# Logger_L072CB_LiPo_Flash_EEprom.net
KiCad netlist of a schematic drawn in Altium Designer
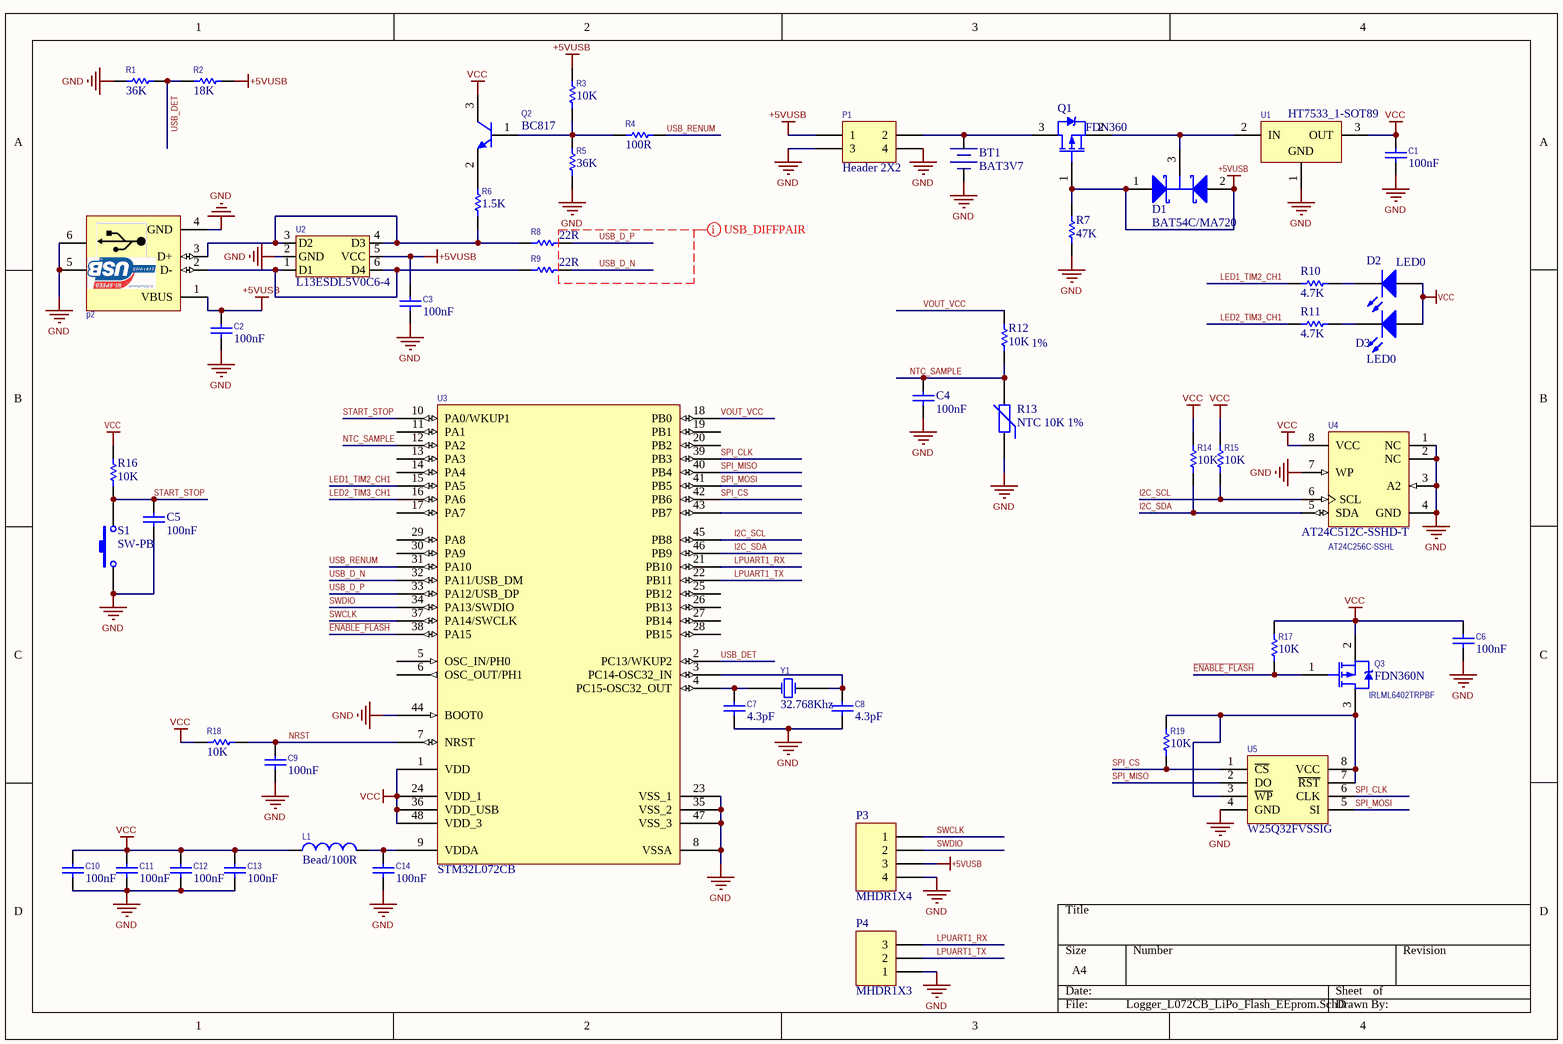
[diagram p0: Logger_L072CB_LiPo_Flash_EEprom.SchDoc]

(export (version "E")
  (design (tool "Eeschema 10.0.6"))
  (components
    (comp (ref "BT1")
      (value "BAT3V7")
      (footprint "BTH2032-smd")
      (description "Battry Backup")
      (fields (field (name "DESIGNER") "Abbas Basereh"))
      (libsource (lib "Mofidi3D") (part "Battry Backup"))
    )
    (comp (ref "C1")
      (value "100nF")
      (footprint "CAP0603")
      (description "Capacitor")
      (fields (field (name "PUBLISHER") "Altium Limited"))
      (libsource (lib "Miscellaneous Devices") (part "Cap"))
    )
    (comp (ref "C2")
      (value "100nF")
      (footprint "CAP0603")
      (description "Capacitor")
      (fields (field (name "PUBLISHER") "Altium Limited"))
      (libsource (lib "Miscellaneous Devices") (part "Cap"))
    )
    (comp (ref "C3")
      (value "100nF")
      (footprint "CAP0603")
      (description "Capacitor")
      (fields (field (name "PUBLISHER") "Altium Limited"))
      (libsource (lib "Miscellaneous Devices") (part "Cap"))
    )
    (comp (ref "C4")
      (value "100nF")
      (footprint "CAP0603")
      (description "Capacitor")
      (fields (field (name "PUBLISHER") "Altium Limited"))
      (libsource (lib "Miscellaneous Devices") (part "Cap"))
    )
    (comp (ref "C5")
      (value "100nF")
      (footprint "CAP0603")
      (description "Capacitor")
      (fields (field (name "PUBLISHER") "Altium Limited"))
      (libsource (lib "Miscellaneous Devices") (part "Cap"))
    )
    (comp (ref "C6")
      (value "100nF")
      (footprint "CAP0603")
      (description "Capacitor")
      (fields (field (name "PUBLISHER") "Altium Limited"))
      (libsource (lib "Miscellaneous Devices") (part "Cap"))
    )
    (comp (ref "C7")
      (value "4.3pF")
      (footprint "CAP0603")
      (description "Capacitor")
      (fields (field (name "PUBLISHER") "Altium Limited"))
      (libsource (lib "Miscellaneous Devices") (part "Cap"))
    )
    (comp (ref "C8")
      (value "4.3pF")
      (footprint "CAP0603")
      (description "Capacitor")
      (fields (field (name "PUBLISHER") "Altium Limited"))
      (libsource (lib "Miscellaneous Devices") (part "Cap"))
    )
    (comp (ref "C9")
      (value "100nF")
      (footprint "CAP0603")
      (description "Capacitor")
      (fields (field (name "PUBLISHER") "Altium Limited"))
      (libsource (lib "Miscellaneous Devices") (part "Cap"))
    )
    (comp (ref "C10")
      (value "100nF")
      (footprint "CAP0603")
      (description "Capacitor")
      (fields (field (name "PUBLISHER") "Altium Limited"))
      (libsource (lib "Miscellaneous Devices") (part "Cap"))
    )
    (comp (ref "C11")
      (value "100nF")
      (footprint "CAP0603")
      (description "Capacitor")
      (fields (field (name "PUBLISHER") "Altium Limited"))
      (libsource (lib "Miscellaneous Devices") (part "Cap"))
    )
    (comp (ref "C12")
      (value "100nF")
      (footprint "CAP0603")
      (description "Capacitor")
      (fields (field (name "PUBLISHER") "Altium Limited"))
      (libsource (lib "Miscellaneous Devices") (part "Cap"))
    )
    (comp (ref "C13")
      (value "100nF")
      (footprint "CAP0603")
      (description "Capacitor")
      (fields (field (name "PUBLISHER") "Altium Limited"))
      (libsource (lib "Miscellaneous Devices") (part "Cap"))
    )
    (comp (ref "C14")
      (value "100nF")
      (footprint "CAP0603")
      (description "Capacitor")
      (fields (field (name "PUBLISHER") "Altium Limited"))
      (libsource (lib "Miscellaneous Devices") (part "Cap"))
    )
    (comp (ref "D1")
      (value "BAT54C/MA720")
      (footprint "SOT23_N")
      (description "Schottky Barrier Double Diode")
      (fields (field (name "PUBLISHER") "Altium Limited"))
      (libsource (lib "Philips Discrete Diode - Schottky") (part "BAT54C"))
    )
    (comp (ref "D2")
      (value "LED0")
      (footprint "LED_0805")
      (description "Typical INFRARED GaAs LED")
      (fields (field (name "PUBLISHER") "Altium Limited"))
      (libsource (lib "Miscellaneous Devices") (part "LED0"))
    )
    (comp (ref "D3")
      (value "LED0")
      (footprint "LED_0805")
      (description "Typical INFRARED GaAs LED")
      (fields (field (name "PUBLISHER") "Altium Limited"))
      (libsource (lib "Miscellaneous Devices") (part "LED0"))
    )
    (comp (ref "L1")
      (value "Bead/100R")
      (footprint "IND0805")
      (description "Inductor")
      (fields (field (name "PUBLISHER") "Altium Limited"))
      (libsource (lib "Miscellaneous Devices") (part "Inductor"))
    )
    (comp (ref "P1")
      (value "Header 2X2")
      (footprint "HDR2X2")
      (description "Header, 2-Pin, Dual row")
      (fields (field (name "PUBLISHER") "Altium Limited"))
      (libsource (lib "Miscellaneous Connectors") (part "Header 2X2"))
    )
    (comp (ref "p2")
      (value "USB Connector")
      (footprint "USB A TYPE Right Angle")
      (description "USB Connector-A Type")
      (fields (field (name "DESIGNER") "ABBAS BASEREH") (field (name "PUBLISHER") "ABBAS BASEREH"))
      (libsource (lib "Mofidi3D") (part "USB A CONNECTOR"))
    )
    (comp (ref "P3")
      (value "MHDR1X4")
      (footprint "HDR1X4")
      (description "Header, 4-Pin")
      (fields (field (name "PUBLISHER") "Altium Limited"))
      (libsource (lib "Miscellaneous Connectors") (part "MHDR1X4"))
    )
    (comp (ref "P4")
      (value "MHDR1X3")
      (footprint "HDR1X3")
      (description "Header, 3-Pin")
      (fields (field (name "PUBLISHER") "Altium Limited"))
      (libsource (lib "Miscellaneous Connectors") (part "MHDR1X3"))
    )
    (comp (ref "Q1")
      (value "FDN360")
      (footprint "SOT-23_N")
      (description "HEXFET Power MOSFET")
      (fields (field (name "PUBLISHER") "Altium Limited"))
      (libsource (lib "IR Discrete MOSFET - Power") (part "IRLML5103"))
    )
    (comp (ref "Q2")
      (value "BC817")
      (footprint "SOT23_N")
      (description "45 V, 500 mA NPN general-purpose transistors")
      (fields (field (name "PUBLISHER") "Abbas Basereh"))
      (libsource (lib "Mofidi3D") (part "BC817"))
    )
    (comp (ref "Q3")
      (value "FDN360N")
      (footprint "Micro3_N")
      (description "HEXFET Power MOSFET")
      (fields (field (name "PUBLISHER") "Altium Limited"))
      (libsource (lib "IR Discrete MOSFET - Power") (part "IRLML6401"))
    )
    (comp (ref "R1")
      (value "36K")
      (footprint "RES0603")
      (description "Resistor")
      (fields (field (name "PUBLISHER") "Altium Limited"))
      (libsource (lib "Miscellaneous Devices") (part "Res1"))
    )
    (comp (ref "R2")
      (value "18K")
      (footprint "RES0603")
      (description "Resistor")
      (fields (field (name "PUBLISHER") "Altium Limited"))
      (libsource (lib "Miscellaneous Devices") (part "Res1"))
    )
    (comp (ref "R3")
      (value "10K")
      (footprint "RES0603")
      (description "Resistor")
      (fields (field (name "PUBLISHER") "Altium Limited"))
      (libsource (lib "Miscellaneous Devices") (part "Res1"))
    )
    (comp (ref "R4")
      (value "100R")
      (footprint "RES0603")
      (description "Resistor")
      (fields (field (name "PUBLISHER") "Altium Limited"))
      (libsource (lib "Miscellaneous Devices") (part "Res1"))
    )
    (comp (ref "R5")
      (value "36K")
      (footprint "RES0603")
      (description "Resistor")
      (fields (field (name "PUBLISHER") "Altium Limited"))
      (libsource (lib "Miscellaneous Devices") (part "Res1"))
    )
    (comp (ref "R6")
      (value "1.5K")
      (footprint "RES0603")
      (description "Resistor")
      (fields (field (name "PUBLISHER") "Altium Limited"))
      (libsource (lib "Miscellaneous Devices") (part "Res1"))
    )
    (comp (ref "R7")
      (value "47K")
      (footprint "RES0603")
      (description "Resistor")
      (fields (field (name "Comment") "Res1") (field (name "PUBLISHER") "Altium Limited"))
      (libsource (lib "Miscellaneous Devices") (part "Res1"))
    )
    (comp (ref "R8")
      (value "22R")
      (footprint "RES0603")
      (description "Resistor")
      (fields (field (name "PUBLISHER") "Altium Limited"))
      (libsource (lib "Miscellaneous Devices") (part "Res1"))
    )
    (comp (ref "R9")
      (value "22R")
      (footprint "RES0603")
      (description "Resistor")
      (fields (field (name "PUBLISHER") "Altium Limited"))
      (libsource (lib "Miscellaneous Devices") (part "Res1"))
    )
    (comp (ref "R10")
      (value "4.7K")
      (footprint "RES0603")
      (description "Resistor")
      (fields (field (name "Comment") "Res1") (field (name "PUBLISHER") "Altium Limited"))
      (libsource (lib "Miscellaneous Devices") (part "Res1"))
    )
    (comp (ref "R11")
      (value "4.7K")
      (footprint "RES0603")
      (description "Resistor")
      (fields (field (name "Comment") "Res1") (field (name "PUBLISHER") "Altium Limited"))
      (libsource (lib "Miscellaneous Devices") (part "Res1"))
    )
    (comp (ref "R12")
      (value "1%")
      (footprint "RES0603")
      (description "Resistor")
      (fields (field (name "ALTIUM_VALUE") "10K") (field (name "PUBLISHER") "Altium Limited"))
      (libsource (lib "Miscellaneous Devices") (part "Res1"))
    )
    (comp (ref "R13")
      (value "NTC 10K 1%")
      (footprint "CAP_MLCC_RAD_0.1")
      (description "Varistor (Voltage-Sensitive Resistor)")
      (fields (field (name "PUBLISHER") "Altium Limited"))
      (libsource (lib "Miscellaneous Devices") (part "Res Varistor"))
    )
    (comp (ref "R14")
      (value "10K")
      (footprint "RES0603")
      (description "Resistor")
      (fields (field (name "PUBLISHER") "Altium Limited"))
      (libsource (lib "Miscellaneous Devices") (part "Res1"))
    )
    (comp (ref "R15")
      (value "10K")
      (footprint "RES0603")
      (description "Resistor")
      (fields (field (name "PUBLISHER") "Altium Limited"))
      (libsource (lib "Miscellaneous Devices") (part "Res1"))
    )
    (comp (ref "R16")
      (value "10K")
      (footprint "RES0603")
      (description "Resistor")
      (fields (field (name "PUBLISHER") "Altium Limited"))
      (libsource (lib "Miscellaneous Devices") (part "Res1"))
    )
    (comp (ref "R17")
      (value "10K")
      (footprint "RES0603")
      (description "Resistor")
      (fields (field (name "PUBLISHER") "Altium Limited"))
      (libsource (lib "Miscellaneous Devices") (part "Res1"))
    )
    (comp (ref "R18")
      (value "10K")
      (footprint "RES0603")
      (description "Resistor")
      (fields (field (name "PUBLISHER") "Altium Limited"))
      (libsource (lib "Miscellaneous Devices") (part "Res1"))
    )
    (comp (ref "R19")
      (value "10K")
      (footprint "RES0603")
      (description "Resistor")
      (fields (field (name "PUBLISHER") "Altium Limited"))
      (libsource (lib "Miscellaneous Devices") (part "Res1"))
    )
    (comp (ref "S1")
      (value "SW-PB")
      (footprint "SW-4PIN-SMD")
      (description "Switch")
      (fields (field (name "PUBLISHER") "Altium Limited"))
      (libsource (lib "Miscellaneous Devices") (part "SW-PB"))
    )
    (comp (ref "U1")
      (value "HT7533_1-SOT89")
      (footprint "SOT89N")
      (description "100mA Low Power LDO, Output Voltage 3.3V, SOT89 Pkg")
      (libsource (lib "Holtek Semiconductor Power Management") (part "HT7533_1-SOT89"))
    )
    (comp (ref "U2")
      (value "L13ESDL5V0C6-4")
      (footprint "Holtek Semiconductor Power Management:SOT23-6_M")
      (description "ESD PROTECTION DEVICE")
      (libsource (lib "Mofidi3D") (part "USBUFxxW6"))
    )
    (comp (ref "U3")
      (value "STM32L072CB")
      (footprint "LQFP48_N")
      (description "STM32 ARM-based 32-bit MCU with 64 Kbytes Flash, 48-pin LQFP, Industrial Temperature")
      (fields (field (name "PUBLISHER") "Altium Limited"))
      (libsource (lib "ST Microcontroller 32-Bit STM32") (part "STM32F103C8T6"))
    )
    (comp (ref "U4")
      (value "AT24C512C-SSHD-T")
      (footprint "SO-8N")
      (description "I2C-Compatible (2-wire) Serial EEPROM\r\n512-Kbit (65,536 x 8)")
      (fields (field (name "PUBLISHER") "Altium Limited"))
      (libsource (lib "Atmel Memory Serial EEPROM") (part "AT24C08BN-SP25-B"))
    )
    (comp (ref "U5")
      (value "W25Q32FVSSIG")
      (footprint "8S2_M")
      (description "SERIAL FLASH MEMORY WITH DUAL, QUAD SPI")
      (libsource (lib "Mofidi3D") (part "W25Q"))
    )
    (comp (ref "Y1")
      (value "32.768Khz")
      (footprint "CM415")
      (description "XTAL Crystal")
      (fields (field (name "DESIGNER") "ABBAS BASEREH"))
      (libsource (lib "Mofidi3D") (part "XTAL_Crystal"))
    )
  )
  (nets
    (net (code "1") (name "+5VUSB") (class "Default")
      (node (ref "C2") (pin "1") (pinfunction "1_1") (pintype "passive"))
      (node (ref "C3") (pin "2") (pinfunction "2_2") (pintype "passive"))
      (node (ref "D1") (pin "1") (pinfunction "A1_1") (pintype "passive"))
      (node (ref "D1") (pin "2") (pinfunction "A2_2") (pintype "passive"))
      (node (ref "P1") (pin "1") (pinfunction "1_1") (pintype "passive"))
      (node (ref "P3") (pin "3") (pinfunction "3_3") (pintype "passive"))
      (node (ref "Q1") (pin "1") (pinfunction "G_1") (pintype "passive"))
      (node (ref "R2") (pin "1") (pinfunction "1_1") (pintype "passive"))
      (node (ref "R3") (pin "1") (pinfunction "1_1") (pintype "passive"))
      (node (ref "R7") (pin "1") (pinfunction "1_1") (pintype "passive"))
      (node (ref "U2") (pin "5") (pinfunction "VCC_5") (pintype "passive"))
      (node (ref "p2") (pin "1") (pinfunction "VBUS_1") (pintype "power_in"))
    )
    (net (code "2") (name "/I2C_SCL") (class "Default")
      (node (ref "R15") (pin "2") (pinfunction "2_2") (pintype "passive"))
      (node (ref "U3") (pin "45") (pinfunction "PB8_45") (pintype "bidirectional"))
      (node (ref "U4") (pin "6") (pinfunction "SCL_6") (pintype "input"))
    )
    (net (code "3") (name "/I2C_SDA") (class "Default")
      (node (ref "R14") (pin "2") (pinfunction "2_2") (pintype "passive"))
      (node (ref "U3") (pin "46") (pinfunction "PB9_46") (pintype "bidirectional"))
      (node (ref "U4") (pin "5") (pinfunction "SDA_5") (pintype "bidirectional"))
    )
    (net (code "4") (name "/LED1_TIM2_CH1") (class "Default")
      (node (ref "R10") (pin "2") (pinfunction "2_2") (pintype "passive"))
      (node (ref "U3") (pin "15") (pinfunction "PA5_15") (pintype "bidirectional"))
    )
    (net (code "5") (name "/LED2_TIM3_CH1") (class "Default")
      (node (ref "R11") (pin "2") (pinfunction "2_2") (pintype "passive"))
      (node (ref "U3") (pin "16") (pinfunction "PA6_16") (pintype "bidirectional"))
    )
    (net (code "6") (name "/LPUART1_RX") (class "Default")
      (node (ref "P4") (pin "3") (pinfunction "3_3") (pintype "passive"))
      (node (ref "U3") (pin "21") (pinfunction "PB10_21") (pintype "bidirectional"))
    )
    (net (code "7") (name "/LPUART1_TX") (class "Default")
      (node (ref "P4") (pin "2") (pinfunction "2_2") (pintype "passive"))
      (node (ref "U3") (pin "22") (pinfunction "PB11_22") (pintype "bidirectional"))
    )
    (net (code "8") (name "/NRST") (class "Default")
      (node (ref "C9") (pin "1") (pinfunction "1_1") (pintype "passive"))
      (node (ref "R18") (pin "1") (pinfunction "1_1") (pintype "passive"))
      (node (ref "U3") (pin "7") (pinfunction "NRST_7") (pintype "bidirectional"))
    )
    (net (code "9") (name "/NTC_SAMPLE") (class "Default")
      (node (ref "C4") (pin "1") (pinfunction "1_1") (pintype "passive"))
      (node (ref "R12") (pin "2") (pinfunction "2_2") (pintype "passive"))
      (node (ref "R13") (pin "2") (pinfunction "2_2") (pintype "passive"))
      (node (ref "U3") (pin "12") (pinfunction "PA2_12") (pintype "bidirectional"))
    )
    (net (code "10") (name "/SPI_CLK") (class "Default")
      (node (ref "U3") (pin "39") (pinfunction "PB3_39") (pintype "bidirectional"))
      (node (ref "U5") (pin "6") (pinfunction "CLK_6") (pintype "passive"))
    )
    (net (code "11") (name "/SPI_CS") (class "Default")
      (node (ref "R19") (pin "2") (pinfunction "2_2") (pintype "passive"))
      (node (ref "U3") (pin "42") (pinfunction "PB6_42") (pintype "bidirectional"))
      (node (ref "U5") (pin "1") (pinfunction "~{CS}_1") (pintype "passive"))
    )
    (net (code "12") (name "/SPI_MISO") (class "Default")
      (node (ref "U3") (pin "40") (pinfunction "PB4_40") (pintype "bidirectional"))
      (node (ref "U5") (pin "2") (pinfunction "DO_2") (pintype "passive"))
    )
    (net (code "13") (name "/SPI_MOSI") (class "Default")
      (node (ref "U3") (pin "41") (pinfunction "PB5_41") (pintype "bidirectional"))
      (node (ref "U5") (pin "5") (pinfunction "SI_5") (pintype "passive"))
    )
    (net (code "14") (name "/START_STOP") (class "Default")
      (node (ref "C5") (pin "2") (pinfunction "2_2") (pintype "passive"))
      (node (ref "R16") (pin "1") (pinfunction "1_1") (pintype "passive"))
      (node (ref "S1") (pin "2") (pinfunction "2_2") (pintype "passive"))
      (node (ref "U3") (pin "10") (pinfunction "PA0/WKUP1_10") (pintype "bidirectional"))
    )
    (net (code "15") (name "/SWCLK") (class "Default")
      (node (ref "P3") (pin "1") (pinfunction "1_1") (pintype "passive"))
      (node (ref "U3") (pin "37") (pinfunction "PA14/SWCLK_37") (pintype "bidirectional"))
    )
    (net (code "16") (name "/SWDIO") (class "Default")
      (node (ref "P3") (pin "2") (pinfunction "2_2") (pintype "passive"))
      (node (ref "U3") (pin "34") (pinfunction "PA13/SWDIO_34") (pintype "bidirectional"))
    )
    (net (code "17") (name "/USB_DET") (class "Default")
      (node (ref "R1") (pin "2") (pinfunction "2_2") (pintype "passive"))
      (node (ref "R2") (pin "2") (pinfunction "2_2") (pintype "passive"))
      (node (ref "U3") (pin "2") (pinfunction "PC13/WKUP2_2") (pintype "bidirectional"))
    )
    (net (code "18") (name "/USB_D_N") (class "Default")
      (node (ref "R9") (pin "1") (pinfunction "1_1") (pintype "passive"))
      (node (ref "U3") (pin "32") (pinfunction "PA11/USB_DM_32") (pintype "bidirectional"))
    )
    (net (code "19") (name "/USB_D_P") (class "Default")
      (node (ref "R8") (pin "1") (pinfunction "1_1") (pintype "passive"))
      (node (ref "U3") (pin "33") (pinfunction "PA12/USB_DP_33") (pintype "bidirectional"))
    )
    (net (code "20") (name "/USB_RENUM") (class "Default")
      (node (ref "R4") (pin "1") (pinfunction "1_1") (pintype "passive"))
      (node (ref "U3") (pin "31") (pinfunction "PA10_31") (pintype "bidirectional"))
    )
    (net (code "21") (name "/VOUT_VCC") (class "Default")
      (node (ref "R12") (pin "1") (pinfunction "1_1") (pintype "passive"))
      (node (ref "U3") (pin "18") (pinfunction "PB0_18") (pintype "bidirectional"))
    )
    (net (code "22") (name "/~{ENABLE_FLASH}") (class "Default")
      (node (ref "Q3") (pin "1") (pinfunction "G_1") (pintype "passive"))
      (node (ref "R17") (pin "2") (pinfunction "2_2") (pintype "passive"))
      (node (ref "U3") (pin "38") (pinfunction "PA15_38") (pintype "bidirectional"))
    )
    (net (code "23") (name "GND") (class "Default")
      (node (ref "BT1") (pin "2") (pinfunction "-_2") (pintype "passive"))
      (node (ref "C1") (pin "2") (pinfunction "2_2") (pintype "passive"))
      (node (ref "C10") (pin "2") (pinfunction "2_2") (pintype "passive"))
      (node (ref "C11") (pin "2") (pinfunction "2_2") (pintype "passive"))
      (node (ref "C12") (pin "2") (pinfunction "2_2") (pintype "passive"))
      (node (ref "C13") (pin "2") (pinfunction "2_2") (pintype "passive"))
      (node (ref "C14") (pin "2") (pinfunction "2_2") (pintype "passive"))
      (node (ref "C2") (pin "2") (pinfunction "2_2") (pintype "passive"))
      (node (ref "C3") (pin "1") (pinfunction "1_1") (pintype "passive"))
      (node (ref "C4") (pin "2") (pinfunction "2_2") (pintype "passive"))
      (node (ref "C5") (pin "1") (pinfunction "1_1") (pintype "passive"))
      (node (ref "C6") (pin "2") (pinfunction "2_2") (pintype "passive"))
      (node (ref "C7") (pin "2") (pinfunction "2_2") (pintype "passive"))
      (node (ref "C8") (pin "2") (pinfunction "2_2") (pintype "passive"))
      (node (ref "C9") (pin "2") (pinfunction "2_2") (pintype "passive"))
      (node (ref "P1") (pin "3") (pinfunction "3_3") (pintype "passive"))
      (node (ref "P1") (pin "4") (pinfunction "4_4") (pintype "passive"))
      (node (ref "P3") (pin "4") (pinfunction "4_4") (pintype "passive"))
      (node (ref "P4") (pin "1") (pinfunction "1_1") (pintype "passive"))
      (node (ref "R1") (pin "1") (pinfunction "1_1") (pintype "passive"))
      (node (ref "R13") (pin "1") (pinfunction "1_1") (pintype "passive"))
      (node (ref "R5") (pin "1") (pinfunction "1_1") (pintype "passive"))
      (node (ref "R7") (pin "2") (pinfunction "2_2") (pintype "passive"))
      (node (ref "S1") (pin "1") (pinfunction "1_1") (pintype "passive"))
      (node (ref "U1") (pin "1") (pinfunction "GND_1") (pintype "power_in"))
      (node (ref "U2") (pin "2") (pinfunction "GND_2") (pintype "passive"))
      (node (ref "U3") (pin "23") (pinfunction "VSS_1_23") (pintype "power_in"))
      (node (ref "U3") (pin "35") (pinfunction "VSS_2_35") (pintype "power_in"))
      (node (ref "U3") (pin "44") (pinfunction "BOOT0_44") (pintype "input"))
      (node (ref "U3") (pin "47") (pinfunction "VSS_3_47") (pintype "power_in"))
      (node (ref "U3") (pin "8") (pinfunction "VSSA_8") (pintype "power_in"))
      (node (ref "U4") (pin "1") (pinfunction "NC_1") (pintype "passive"))
      (node (ref "U4") (pin "2") (pinfunction "NC_2") (pintype "passive"))
      (node (ref "U4") (pin "3") (pinfunction "A2_3") (pintype "input"))
      (node (ref "U4") (pin "4") (pinfunction "GND_4") (pintype "power_in"))
      (node (ref "U4") (pin "7") (pinfunction "WP_7") (pintype "input"))
      (node (ref "U5") (pin "4") (pinfunction "GND_4") (pintype "passive"))
      (node (ref "p2") (pin "4") (pinfunction "GND_4") (pintype "power_in"))
      (node (ref "p2") (pin "5") (pinfunction "MH_5") (pintype "power_in"))
      (node (ref "p2") (pin "6") (pinfunction "MH_6") (pintype "power_in"))
    )
    (net (code "24") (name "Net-(BT1-+)") (class "Default")
      (node (ref "BT1") (pin "1") (pinfunction "+_1") (pintype "passive"))
      (node (ref "P1") (pin "2") (pinfunction "2_2") (pintype "passive"))
      (node (ref "Q1") (pin "3") (pinfunction "D_3") (pintype "passive"))
    )
    (net (code "25") (name "Net-(D1-K)") (class "Default")
      (node (ref "D1") (pin "3") (pinfunction "K_3") (pintype "passive"))
      (node (ref "Q1") (pin "2") (pinfunction "S_2") (pintype "passive"))
      (node (ref "U1") (pin "2") (pinfunction "IN_2") (pintype "power_in"))
    )
    (net (code "26") (name "Net-(D2-K)") (class "Default")
      (node (ref "D2") (pin "2") (pinfunction "K_2") (pintype "passive"))
      (node (ref "R10") (pin "1") (pinfunction "1_1") (pintype "passive"))
    )
    (net (code "27") (name "Net-(D3-K)") (class "Default")
      (node (ref "D3") (pin "2") (pinfunction "K_2") (pintype "passive"))
      (node (ref "R11") (pin "1") (pinfunction "1_1") (pintype "passive"))
    )
    (net (code "28") (name "Net-(Q2-B)") (class "Default")
      (node (ref "Q2") (pin "1") (pinfunction "B_1") (pintype "passive"))
      (node (ref "R3") (pin "2") (pinfunction "2_2") (pintype "passive"))
      (node (ref "R4") (pin "2") (pinfunction "2_2") (pintype "passive"))
      (node (ref "R5") (pin "2") (pinfunction "2_2") (pintype "passive"))
    )
    (net (code "29") (name "Net-(Q2-E)") (class "Default")
      (node (ref "Q2") (pin "2") (pinfunction "E_2") (pintype "passive"))
      (node (ref "R6") (pin "1") (pinfunction "1_1") (pintype "passive"))
    )
    (net (code "30") (name "Net-(Q3-D)") (class "Default")
      (node (ref "Q3") (pin "3") (pinfunction "D_3") (pintype "passive"))
      (node (ref "R19") (pin "1") (pinfunction "1_1") (pintype "passive"))
      (node (ref "U5") (pin "3") (pinfunction "~{WP}_3") (pintype "passive"))
      (node (ref "U5") (pin "7") (pinfunction "~{RST}_7") (pintype "passive"))
      (node (ref "U5") (pin "8") (pinfunction "VCC_8") (pintype "passive"))
    )
    (net (code "31") (name "Net-(U2-D1)") (class "Default")
      (node (ref "R9") (pin "2") (pinfunction "2_2") (pintype "passive"))
      (node (ref "U2") (pin "1") (pinfunction "D1_1") (pintype "passive"))
      (node (ref "U2") (pin "6") (pinfunction "D4_6") (pintype "passive"))
      (node (ref "p2") (pin "2") (pinfunction "D-_2") (pintype "bidirectional"))
    )
    (net (code "32") (name "Net-(U2-D2)") (class "Default")
      (node (ref "R6") (pin "2") (pinfunction "2_2") (pintype "passive"))
      (node (ref "R8") (pin "2") (pinfunction "2_2") (pintype "passive"))
      (node (ref "U2") (pin "3") (pinfunction "D2_3") (pintype "passive"))
      (node (ref "U2") (pin "4") (pinfunction "D3_4") (pintype "passive"))
      (node (ref "p2") (pin "3") (pinfunction "D+_3") (pintype "bidirectional"))
    )
    (net (code "33") (name "Net-(U3-PC14-OSC32_IN)") (class "Default")
      (node (ref "C8") (pin "1") (pinfunction "1_1") (pintype "passive"))
      (node (ref "U3") (pin "3") (pinfunction "PC14-OSC32_IN_3") (pintype "bidirectional"))
      (node (ref "Y1") (pin "1") (pinfunction "OSC1_1") (pintype "passive"))
    )
    (net (code "34") (name "Net-(U3-PC15-OSC32_OUT)") (class "Default")
      (node (ref "C7") (pin "1") (pinfunction "1_1") (pintype "passive"))
      (node (ref "U3") (pin "4") (pinfunction "PC15-OSC32_OUT_4") (pintype "bidirectional"))
      (node (ref "Y1") (pin "2") (pinfunction "OSC2_2") (pintype "passive"))
    )
    (net (code "35") (name "Net-(U3-VDDA)") (class "Default")
      (node (ref "C14") (pin "1") (pinfunction "1_1") (pintype "passive"))
      (node (ref "L1") (pin "2") (pinfunction "2_2") (pintype "passive"))
      (node (ref "U3") (pin "9") (pinfunction "VDDA_9") (pintype "power_in"))
    )
    (net (code "36") (name "VCC") (class "Default")
      (node (ref "C1") (pin "1") (pinfunction "1_1") (pintype "passive"))
      (node (ref "C10") (pin "1") (pinfunction "1_1") (pintype "passive"))
      (node (ref "C11") (pin "1") (pinfunction "1_1") (pintype "passive"))
      (node (ref "C12") (pin "1") (pinfunction "1_1") (pintype "passive"))
      (node (ref "C13") (pin "1") (pinfunction "1_1") (pintype "passive"))
      (node (ref "C6") (pin "1") (pinfunction "1_1") (pintype "passive"))
      (node (ref "D2") (pin "1") (pinfunction "A_1") (pintype "passive"))
      (node (ref "D3") (pin "1") (pinfunction "A_1") (pintype "passive"))
      (node (ref "L1") (pin "1") (pinfunction "1_1") (pintype "passive"))
      (node (ref "Q2") (pin "3") (pinfunction "C_3") (pintype "passive"))
      (node (ref "Q3") (pin "2") (pinfunction "S_2") (pintype "passive"))
      (node (ref "R14") (pin "1") (pinfunction "1_1") (pintype "passive"))
      (node (ref "R15") (pin "1") (pinfunction "1_1") (pintype "passive"))
      (node (ref "R16") (pin "2") (pinfunction "2_2") (pintype "passive"))
      (node (ref "R17") (pin "1") (pinfunction "1_1") (pintype "passive"))
      (node (ref "R18") (pin "2") (pinfunction "2_2") (pintype "passive"))
      (node (ref "U1") (pin "3") (pinfunction "OUT_3") (pintype "power_in"))
      (node (ref "U3") (pin "1") (pinfunction "VDD_1") (pintype "power_in"))
      (node (ref "U3") (pin "24") (pinfunction "VDD_1_24") (pintype "power_in"))
      (node (ref "U3") (pin "36") (pinfunction "VDD_USB_36") (pintype "power_in"))
      (node (ref "U3") (pin "48") (pinfunction "VDD_3_48") (pintype "power_in"))
      (node (ref "U4") (pin "8") (pinfunction "VCC_8") (pintype "power_in"))
    )
    (net (code "37") (name "unconnected-(U3-OSC_IN{slash}PH0-Pad5)") (class "Default")
      (node (ref "U3") (pin "5") (pinfunction "OSC_IN/PH0_5") (pintype "input"))
    )
    (net (code "38") (name "unconnected-(U3-OSC_OUT{slash}PH1-Pad6)") (class "Default")
      (node (ref "U3") (pin "6") (pinfunction "OSC_OUT/PH1_6") (pintype "output"))
    )
    (net (code "39") (name "unconnected-(U3-PA1-Pad11)") (class "Default")
      (node (ref "U3") (pin "11") (pinfunction "PA1_11") (pintype "bidirectional"))
    )
    (net (code "40") (name "unconnected-(U3-PA3-Pad13)") (class "Default")
      (node (ref "U3") (pin "13") (pinfunction "PA3_13") (pintype "bidirectional"))
    )
    (net (code "41") (name "unconnected-(U3-PA4-Pad14)") (class "Default")
      (node (ref "U3") (pin "14") (pinfunction "PA4_14") (pintype "bidirectional"))
    )
    (net (code "42") (name "unconnected-(U3-PA7-Pad17)") (class "Default")
      (node (ref "U3") (pin "17") (pinfunction "PA7_17") (pintype "bidirectional"))
    )
    (net (code "43") (name "unconnected-(U3-PA8-Pad29)") (class "Default")
      (node (ref "U3") (pin "29") (pinfunction "PA8_29") (pintype "bidirectional"))
    )
    (net (code "44") (name "unconnected-(U3-PA9-Pad30)") (class "Default")
      (node (ref "U3") (pin "30") (pinfunction "PA9_30") (pintype "bidirectional"))
    )
    (net (code "45") (name "unconnected-(U3-PB1-Pad19)") (class "Default")
      (node (ref "U3") (pin "19") (pinfunction "PB1_19") (pintype "bidirectional"))
    )
    (net (code "46") (name "unconnected-(U3-PB2-Pad20)") (class "Default")
      (node (ref "U3") (pin "20") (pinfunction "PB2_20") (pintype "bidirectional"))
    )
    (net (code "47") (name "unconnected-(U3-PB7-Pad43)") (class "Default")
      (node (ref "U3") (pin "43") (pinfunction "PB7_43") (pintype "bidirectional"))
    )
    (net (code "48") (name "unconnected-(U3-PB12-Pad25)") (class "Default")
      (node (ref "U3") (pin "25") (pinfunction "PB12_25") (pintype "bidirectional"))
    )
    (net (code "49") (name "unconnected-(U3-PB13-Pad26)") (class "Default")
      (node (ref "U3") (pin "26") (pinfunction "PB13_26") (pintype "bidirectional"))
    )
    (net (code "50") (name "unconnected-(U3-PB14-Pad27)") (class "Default")
      (node (ref "U3") (pin "27") (pinfunction "PB14_27") (pintype "bidirectional"))
    )
    (net (code "51") (name "unconnected-(U3-PB15-Pad28)") (class "Default")
      (node (ref "U3") (pin "28") (pinfunction "PB15_28") (pintype "bidirectional"))
    )
  )
)
